# ADC_PLL.net
KiCad netlist of a schematic drawn in Altium Designer
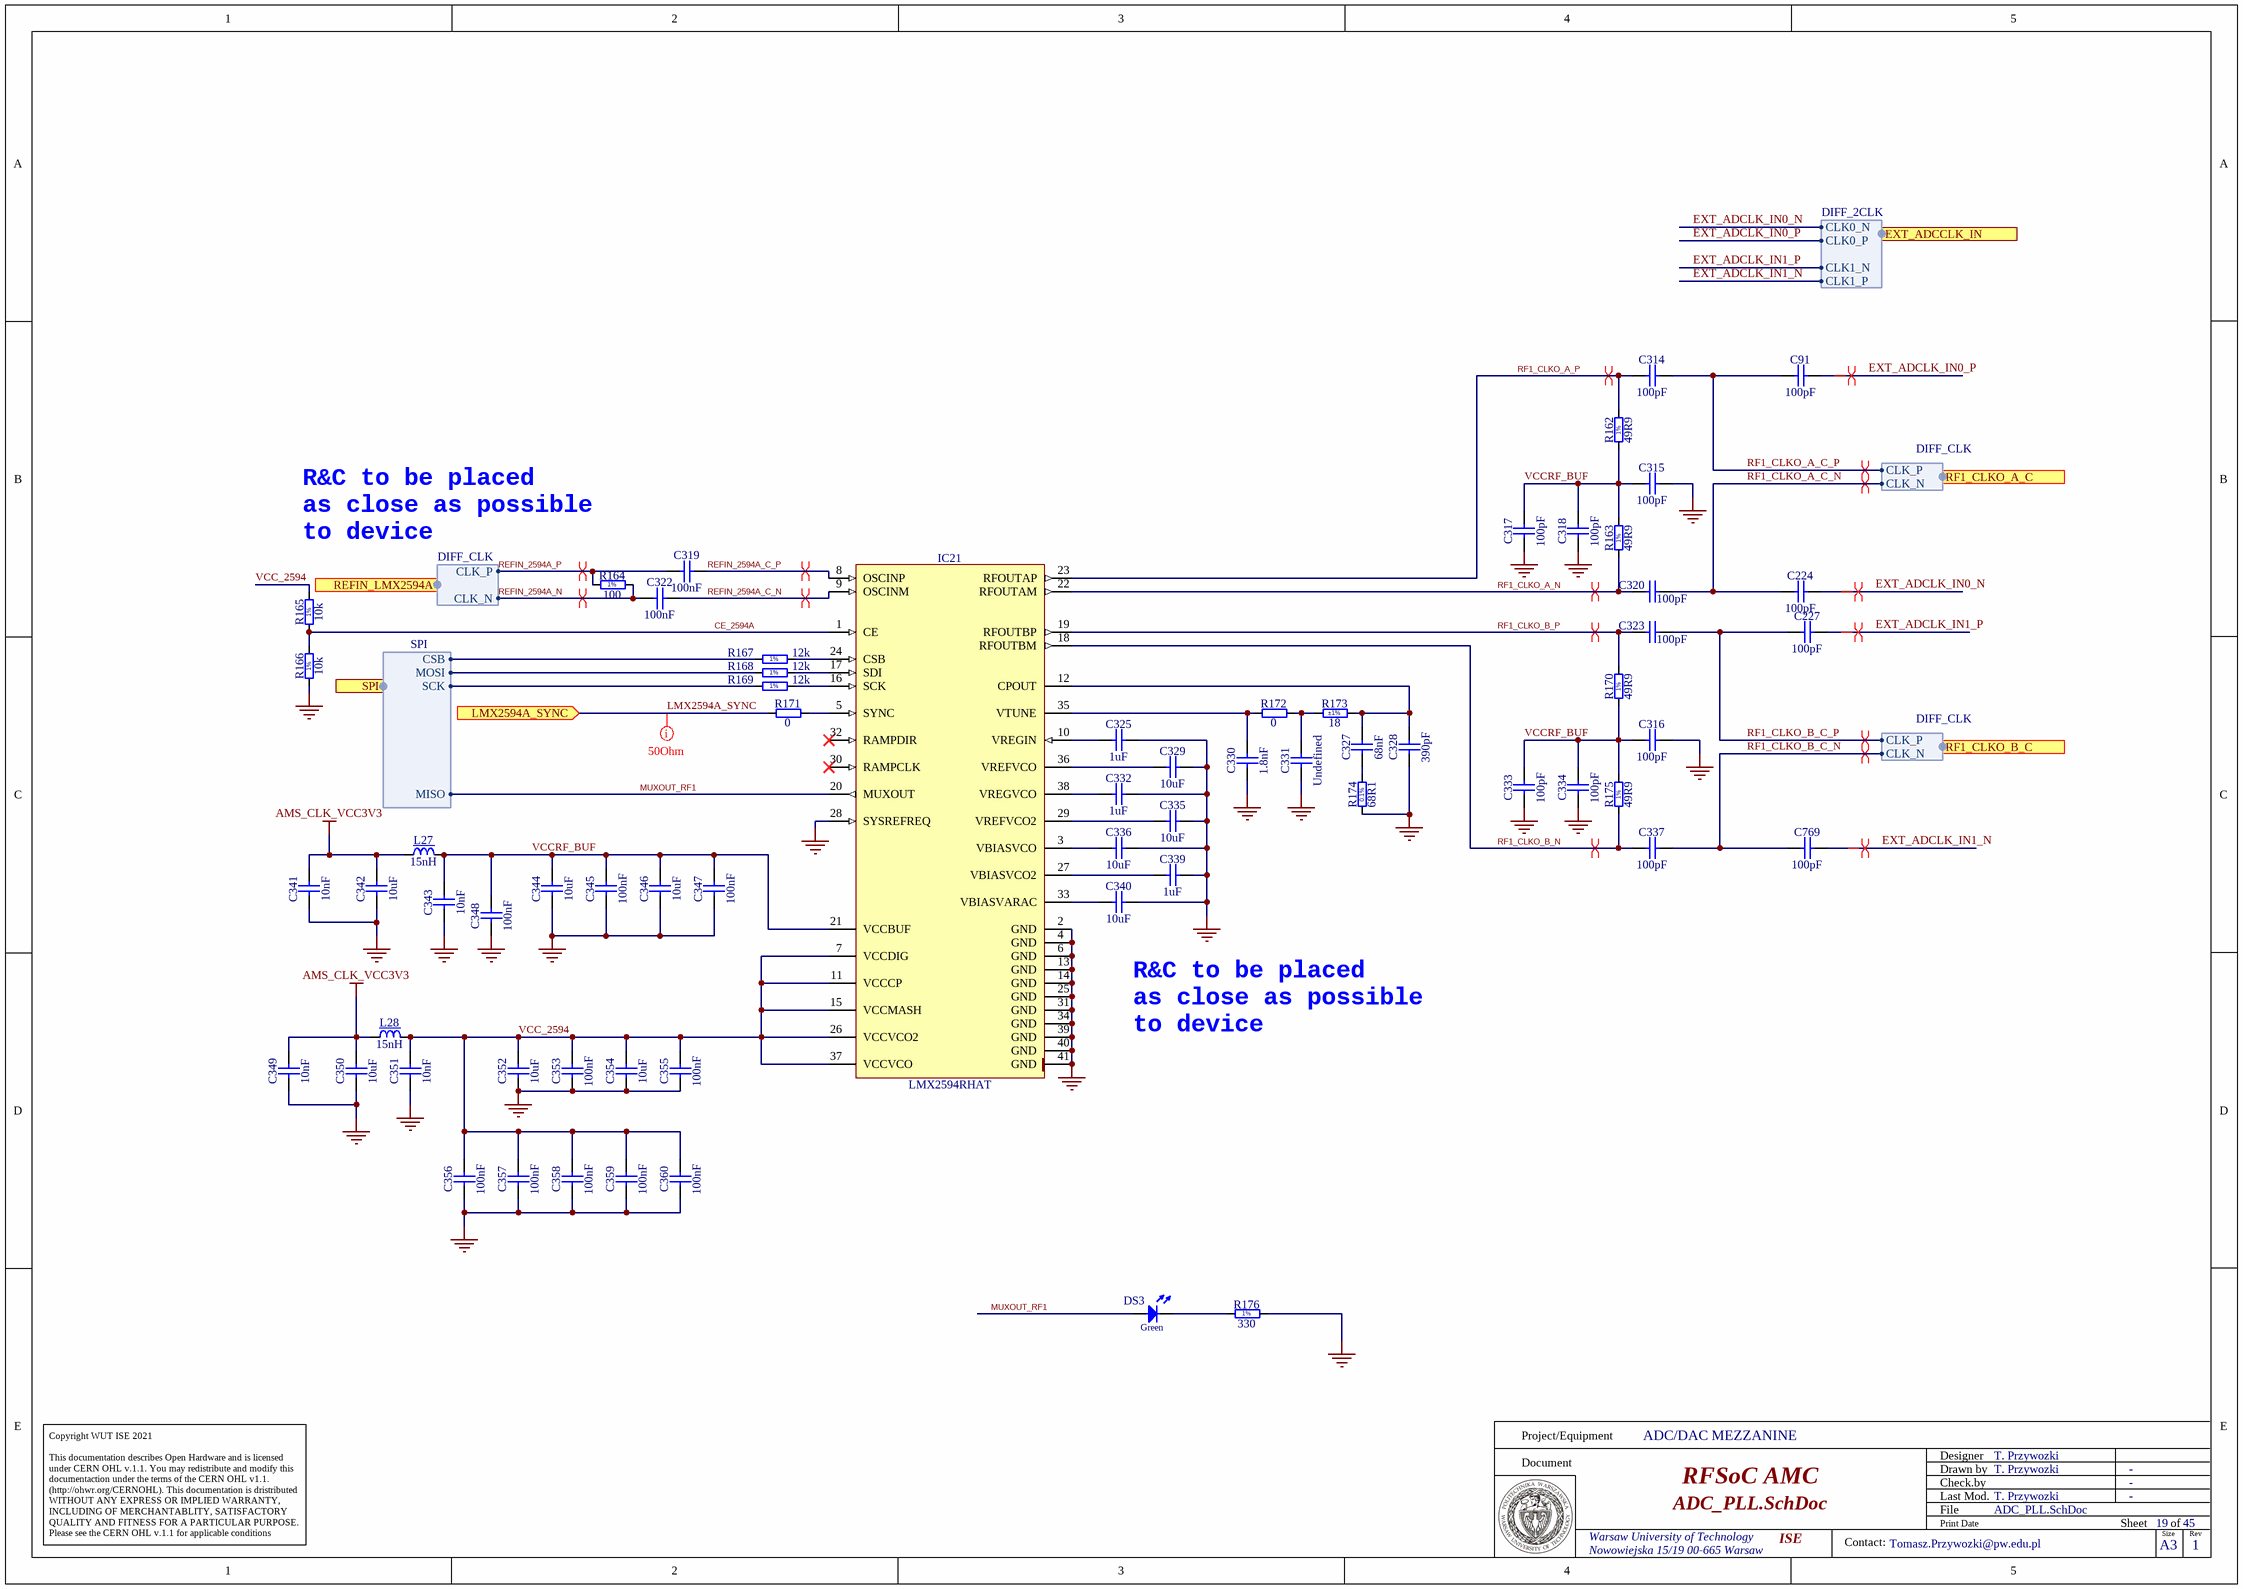
[diagram p0: ADC_PLL.SchDoc]

(export (version "E")
  (design (tool "Eeschema 10.0.6"))
  (components
    (comp (ref "C91")
      (value "100pF")
      (footprint "CAPC1005X55N")
      (description "Non-polarised capacitor")
      (fields
        (field (name "PART NUMBER") "CC0402_100PF_25V_5%_C0G_KEMET_HiQ-CBR")
        (field (name "VOLTAGE") "25V")
        (field (name "AUTHOR") "CERN DEM MR")
      )
      (libsource (lib "Capacitors") (part "Capacitor - non polarized"))
    )
    (comp (ref "C224")
      (value "100pF")
      (footprint "CAPC1005X55N")
      (description "Non-polarised capacitor")
      (fields
        (field (name "PART NUMBER") "CC0402_100PF_25V_5%_C0G_KEMET_HiQ-CBR")
        (field (name "VOLTAGE") "25V")
        (field (name "AUTHOR") "CERN DEM MR")
      )
      (libsource (lib "Capacitors") (part "Capacitor - non polarized"))
    )
    (comp (ref "C227")
      (value "100pF")
      (footprint "CAPC1005X55N")
      (description "Non-polarised capacitor")
      (fields
        (field (name "PART NUMBER") "CC0402_100PF_25V_5%_C0G_KEMET_HiQ-CBR")
        (field (name "VOLTAGE") "25V")
        (field (name "AUTHOR") "CERN DEM MR")
      )
      (libsource (lib "Capacitors") (part "Capacitor - non polarized"))
    )
    (comp (ref "C314")
      (value "100pF")
      (footprint "CAPC1005X55N")
      (description "Non-polarised capacitor")
      (fields
        (field (name "PART NUMBER") "CC0402_100PF_25V_5%_C0G_KEMET_HiQ-CBR")
        (field (name "VOLTAGE") "25V")
        (field (name "AUTHOR") "CERN DEM MR")
      )
      (libsource (lib "Capacitors") (part "Capacitor - non polarized"))
    )
    (comp (ref "C315")
      (value "100pF")
      (footprint "CAPC1005X55N")
      (description "Non-polarised capacitor")
      (fields
        (field (name "PART NUMBER") "CC0402_100PF_25V_5%_C0G_KEMET_HiQ-CBR")
        (field (name "VOLTAGE") "25V")
        (field (name "AUTHOR") "CERN DEM MR")
      )
      (libsource (lib "Capacitors") (part "Capacitor - non polarized"))
    )
    (comp (ref "C316")
      (value "100pF")
      (footprint "CAPC1005X55N")
      (description "Non-polarised capacitor")
      (fields
        (field (name "PART NUMBER") "CC0402_100PF_25V_5%_C0G_KEMET_HiQ-CBR")
        (field (name "VOLTAGE") "25V")
        (field (name "AUTHOR") "CERN DEM MR")
      )
      (libsource (lib "Capacitors") (part "Capacitor - non polarized"))
    )
    (comp (ref "C317")
      (value "100pF")
      (footprint "CAPC1005X55N")
      (description "Non-polarised capacitor")
      (fields
        (field (name "PART NUMBER") "CC0402_100PF_25V_5%_C0G_KEMET_HiQ-CBR")
        (field (name "VOLTAGE") "25V")
        (field (name "AUTHOR") "CERN DEM MR")
      )
      (libsource (lib "Capacitors") (part "Capacitor - non polarized"))
    )
    (comp (ref "C318")
      (value "100pF")
      (footprint "CAPC1005X55N")
      (description "Non-polarised capacitor")
      (fields
        (field (name "PART NUMBER") "CC0402_100PF_25V_5%_C0G_KEMET_HiQ-CBR")
        (field (name "VOLTAGE") "25V")
        (field (name "AUTHOR") "CERN DEM MR")
      )
      (libsource (lib "Capacitors") (part "Capacitor - non polarized"))
    )
    (comp (ref "C319")
      (value "100nF")
      (footprint "CAPC1005X55N")
      (description "Non-polarised capacitor")
      (fields
        (field (name "PART NUMBER") "CC0402_100NF_25V_10%_X7R_YUDEN_TMK105B7104KVHF")
        (field (name "VOLTAGE") "25V")
        (field (name "AUTHOR") "CERN DEM JLC")
      )
      (libsource (lib "Capacitors") (part "Capacitor - non polarized"))
    )
    (comp (ref "C320")
      (value "100pF")
      (footprint "CAPC1005X55N")
      (description "Non-polarised capacitor")
      (fields
        (field (name "PART NUMBER") "CC0402_100PF_25V_5%_C0G_KEMET_HiQ-CBR")
        (field (name "VOLTAGE") "25V")
        (field (name "AUTHOR") "CERN DEM MR")
      )
      (libsource (lib "Capacitors") (part "Capacitor - non polarized"))
    )
    (comp (ref "C322")
      (value "100nF")
      (footprint "CAPC1005X55N")
      (description "Non-polarised capacitor")
      (fields
        (field (name "PART NUMBER") "CC0402_100NF_25V_10%_X7R_YUDEN_TMK105B7104KVHF")
        (field (name "VOLTAGE") "25V")
        (field (name "AUTHOR") "CERN DEM JLC")
      )
      (libsource (lib "Capacitors") (part "Capacitor - non polarized"))
    )
    (comp (ref "C323")
      (value "100pF")
      (footprint "CAPC1005X55N")
      (description "Non-polarised capacitor")
      (fields
        (field (name "PART NUMBER") "CC0402_100PF_25V_5%_C0G_KEMET_HiQ-CBR")
        (field (name "VOLTAGE") "25V")
        (field (name "AUTHOR") "CERN DEM MR")
      )
      (libsource (lib "Capacitors") (part "Capacitor - non polarized"))
    )
    (comp (ref "C325")
      (value "1uF")
      (footprint "CAPC1005X55N")
      (description "Non-polarised capacitor")
      (fields
        (field (name "PART NUMBER") "CC0402_1UF_16V_10%_X5R")
        (field (name "VOLTAGE") "16V")
        (field (name "AUTHOR") "CERN DEM JLC")
      )
      (libsource (lib "Capacitors") (part "Capacitor - non polarized"))
    )
    (comp (ref "C327")
      (value "68nF")
      (footprint "CAPC1005X55N")
      (description "Non-polarised capacitor")
      (fields
        (field (name "PART NUMBER") "CC0402_68NF_16V_10%_X7R")
        (field (name "VOLTAGE") "16V")
        (field (name "AUTHOR") "CERN DEM JLC")
      )
      (libsource (lib "Capacitors") (part "Capacitor - non polarized"))
    )
    (comp (ref "C328")
      (value "390pF")
      (footprint "CAPC1608X87N")
      (description "Non-polarised capacitor")
      (fields
        (field (name "PART NUMBER") "CC0603_390PF_50V_5%_NP0")
        (field (name "VOLTAGE") "50V")
        (field (name "AUTHOR") "CERN DEM JLC")
      )
      (libsource (lib "Capacitors") (part "Capacitor - non polarized"))
    )
    (comp (ref "C329")
      (value "10uF")
      (footprint "CAPC1608X80N")
      (description "Non-polarised capacitor")
      (fields
        (field (name "PART NUMBER") "CC0603_10UF_10V_10%_X5R")
        (field (name "VOLTAGE") "10V")
        (field (name "AUTHOR") "CERN DEM JLC")
      )
      (libsource (lib "Capacitors") (part "Capacitor - non polarized"))
    )
    (comp (ref "C330")
      (value "1.8nF")
      (footprint "CAPC1608X87N")
      (description "Non-polarised capacitor")
      (fields
        (field (name "PART NUMBER") "CC0603_1.8NF_50V_5%_X7R")
        (field (name "VOLTAGE") "50V")
        (field (name "AUTHOR") "CERN DEM JLC")
      )
      (libsource (lib "Capacitors") (part "Capacitor - non polarized"))
    )
    (comp (ref "C331")
      (value "Undefined")
      (footprint "CAPC1005X55N")
      (description "Non-polarised capacitor")
      (fields (field (name "PART NUMBER") "CC0402_NO-VALUE") (field (name "AUTHOR") "CERN DEM JLC"))
      (libsource (lib "Capacitors") (part "Capacitor - non polarized"))
    )
    (comp (ref "C332")
      (value "1uF")
      (footprint "CAPC1005X55N")
      (description "Non-polarised capacitor")
      (fields
        (field (name "PART NUMBER") "CC0402_1UF_16V_10%_X5R")
        (field (name "VOLTAGE") "16V")
        (field (name "AUTHOR") "CERN DEM JLC")
      )
      (libsource (lib "Capacitors") (part "Capacitor - non polarized"))
    )
    (comp (ref "C333")
      (value "100pF")
      (footprint "CAPC1005X55N")
      (description "Non-polarised capacitor")
      (fields
        (field (name "PART NUMBER") "CC0402_100PF_25V_5%_C0G_KEMET_HiQ-CBR")
        (field (name "VOLTAGE") "25V")
        (field (name "AUTHOR") "CERN DEM MR")
      )
      (libsource (lib "Capacitors") (part "Capacitor - non polarized"))
    )
    (comp (ref "C334")
      (value "100pF")
      (footprint "CAPC1005X55N")
      (description "Non-polarised capacitor")
      (fields
        (field (name "PART NUMBER") "CC0402_100PF_25V_5%_C0G_KEMET_HiQ-CBR")
        (field (name "VOLTAGE") "25V")
        (field (name "AUTHOR") "CERN DEM MR")
      )
      (libsource (lib "Capacitors") (part "Capacitor - non polarized"))
    )
    (comp (ref "C335")
      (value "10uF")
      (footprint "CAPC1608X80N")
      (description "Non-polarised capacitor")
      (fields
        (field (name "PART NUMBER") "CC0603_10UF_10V_10%_X5R")
        (field (name "VOLTAGE") "10V")
        (field (name "AUTHOR") "CERN DEM JLC")
      )
      (libsource (lib "Capacitors") (part "Capacitor - non polarized"))
    )
    (comp (ref "C336")
      (value "10uF")
      (footprint "CAPC1608X80N")
      (description "Non-polarised capacitor")
      (fields
        (field (name "PART NUMBER") "CC0603_10UF_10V_10%_X5R")
        (field (name "VOLTAGE") "10V")
        (field (name "AUTHOR") "CERN DEM JLC")
      )
      (libsource (lib "Capacitors") (part "Capacitor - non polarized"))
    )
    (comp (ref "C337")
      (value "100pF")
      (footprint "CAPC1005X55N")
      (description "Non-polarised capacitor")
      (fields
        (field (name "PART NUMBER") "CC0402_100PF_25V_5%_C0G_KEMET_HiQ-CBR")
        (field (name "VOLTAGE") "25V")
        (field (name "AUTHOR") "CERN DEM MR")
      )
      (libsource (lib "Capacitors") (part "Capacitor - non polarized"))
    )
    (comp (ref "C339")
      (value "1uF")
      (footprint "CAPC1005X55N")
      (description "Non-polarised capacitor")
      (fields
        (field (name "PART NUMBER") "CC0402_1UF_16V_10%_X5R")
        (field (name "VOLTAGE") "16V")
        (field (name "AUTHOR") "CERN DEM JLC")
      )
      (libsource (lib "Capacitors") (part "Capacitor - non polarized"))
    )
    (comp (ref "C340")
      (value "10uF")
      (footprint "CAPC1608X80N")
      (description "Non-polarised capacitor")
      (fields
        (field (name "PART NUMBER") "CC0603_10UF_10V_10%_X5R")
        (field (name "VOLTAGE") "10V")
        (field (name "AUTHOR") "CERN DEM JLC")
      )
      (libsource (lib "Capacitors") (part "Capacitor - non polarized"))
    )
    (comp (ref "C341")
      (value "10nF")
      (footprint "CAPC1005X55N")
      (description "Non-polarised capacitor")
      (fields
        (field (name "PART NUMBER") "CC0402_10NF_16V_10%_X7R")
        (field (name "VOLTAGE") "16V")
        (field (name "AUTHOR") "CERN DEM JLC")
      )
      (libsource (lib "Capacitors") (part "Capacitor - non polarized"))
    )
    (comp (ref "C342")
      (value "10uF")
      (footprint "CAPC1608X80N")
      (description "Non-polarised capacitor")
      (fields
        (field (name "PART NUMBER") "CC0603_10UF_10V_10%_X5R")
        (field (name "VOLTAGE") "10V")
        (field (name "AUTHOR") "CERN DEM JLC")
      )
      (libsource (lib "Capacitors") (part "Capacitor - non polarized"))
    )
    (comp (ref "C343")
      (value "10nF")
      (footprint "CAPC1005X55N")
      (description "Non-polarised capacitor")
      (fields
        (field (name "PART NUMBER") "CC0402_10NF_16V_10%_X7R")
        (field (name "VOLTAGE") "16V")
        (field (name "AUTHOR") "CERN DEM JLC")
      )
      (libsource (lib "Capacitors") (part "Capacitor - non polarized"))
    )
    (comp (ref "C344")
      (value "10uF")
      (footprint "CAPC1608X80N")
      (description "Non-polarised capacitor")
      (fields
        (field (name "PART NUMBER") "CC0603_10UF_10V_10%_X5R")
        (field (name "VOLTAGE") "10V")
        (field (name "AUTHOR") "CERN DEM JLC")
      )
      (libsource (lib "Capacitors") (part "Capacitor - non polarized"))
    )
    (comp (ref "C345")
      (value "100nF")
      (footprint "CAPC1005X55N")
      (description "Non-polarised capacitor")
      (fields
        (field (name "PART NUMBER") "CC0402_100NF_25V_10%_X7R_YUDEN_TMK105B7104KVHF")
        (field (name "VOLTAGE") "25V")
        (field (name "AUTHOR") "CERN DEM JLC")
      )
      (libsource (lib "Capacitors") (part "Capacitor - non polarized"))
    )
    (comp (ref "C346")
      (value "10uF")
      (footprint "CAPC1608X80N")
      (description "Non-polarised capacitor")
      (fields
        (field (name "PART NUMBER") "CC0603_10UF_10V_10%_X5R")
        (field (name "VOLTAGE") "10V")
        (field (name "AUTHOR") "CERN DEM JLC")
      )
      (libsource (lib "Capacitors") (part "Capacitor - non polarized"))
    )
    (comp (ref "C347")
      (value "100nF")
      (footprint "CAPC1005X55N")
      (description "Non-polarised capacitor")
      (fields
        (field (name "PART NUMBER") "CC0402_100NF_25V_10%_X7R_YUDEN_TMK105B7104KVHF")
        (field (name "VOLTAGE") "25V")
        (field (name "AUTHOR") "CERN DEM JLC")
      )
      (libsource (lib "Capacitors") (part "Capacitor - non polarized"))
    )
    (comp (ref "C348")
      (value "100nF")
      (footprint "CAPC1005X55N")
      (description "Non-polarised capacitor")
      (fields
        (field (name "PART NUMBER") "CC0402_100NF_25V_10%_X7R_YUDEN_TMK105B7104KVHF")
        (field (name "VOLTAGE") "25V")
        (field (name "AUTHOR") "CERN DEM JLC")
      )
      (libsource (lib "Capacitors") (part "Capacitor - non polarized"))
    )
    (comp (ref "C349")
      (value "10nF")
      (footprint "CAPC1005X55N")
      (description "Non-polarised capacitor")
      (fields
        (field (name "PART NUMBER") "CC0402_10NF_16V_10%_X7R")
        (field (name "VOLTAGE") "16V")
        (field (name "AUTHOR") "CERN DEM JLC")
      )
      (libsource (lib "Capacitors") (part "Capacitor - non polarized"))
    )
    (comp (ref "C350")
      (value "10uF")
      (footprint "CAPC1608X80N")
      (description "Non-polarised capacitor")
      (fields
        (field (name "PART NUMBER") "CC0603_10UF_10V_10%_X5R")
        (field (name "VOLTAGE") "10V")
        (field (name "AUTHOR") "CERN DEM JLC")
      )
      (libsource (lib "Capacitors") (part "Capacitor - non polarized"))
    )
    (comp (ref "C351")
      (value "10nF")
      (footprint "CAPC1005X55N")
      (description "Non-polarised capacitor")
      (fields
        (field (name "PART NUMBER") "CC0402_10NF_16V_10%_X7R")
        (field (name "VOLTAGE") "16V")
        (field (name "AUTHOR") "CERN DEM JLC")
      )
      (libsource (lib "Capacitors") (part "Capacitor - non polarized"))
    )
    (comp (ref "C352")
      (value "10uF")
      (footprint "CAPC1608X80N")
      (description "Non-polarised capacitor")
      (fields
        (field (name "PART NUMBER") "CC0603_10UF_10V_10%_X5R")
        (field (name "VOLTAGE") "10V")
        (field (name "AUTHOR") "CERN DEM JLC")
      )
      (libsource (lib "Capacitors") (part "Capacitor - non polarized"))
    )
    (comp (ref "C353")
      (value "100nF")
      (footprint "CAPC1005X55N")
      (description "Non-polarised capacitor")
      (fields
        (field (name "PART NUMBER") "CC0402_100NF_25V_10%_X7R_YUDEN_TMK105B7104KVHF")
        (field (name "VOLTAGE") "25V")
        (field (name "AUTHOR") "CERN DEM JLC")
      )
      (libsource (lib "Capacitors") (part "Capacitor - non polarized"))
    )
    (comp (ref "C354")
      (value "10uF")
      (footprint "CAPC1608X80N")
      (description "Non-polarised capacitor")
      (fields
        (field (name "PART NUMBER") "CC0603_10UF_10V_10%_X5R")
        (field (name "VOLTAGE") "10V")
        (field (name "AUTHOR") "CERN DEM JLC")
      )
      (libsource (lib "Capacitors") (part "Capacitor - non polarized"))
    )
    (comp (ref "C355")
      (value "100nF")
      (footprint "CAPC1005X55N")
      (description "Non-polarised capacitor")
      (fields
        (field (name "PART NUMBER") "CC0402_100NF_25V_10%_X7R_YUDEN_TMK105B7104KVHF")
        (field (name "VOLTAGE") "25V")
        (field (name "AUTHOR") "CERN DEM JLC")
      )
      (libsource (lib "Capacitors") (part "Capacitor - non polarized"))
    )
    (comp (ref "C356")
      (value "100nF")
      (footprint "CAPC1005X55N")
      (description "Non-polarised capacitor")
      (fields
        (field (name "PART NUMBER") "CC0402_100NF_25V_10%_X7R_YUDEN_TMK105B7104KVHF")
        (field (name "VOLTAGE") "25V")
        (field (name "AUTHOR") "CERN DEM JLC")
      )
      (libsource (lib "Capacitors") (part "Capacitor - non polarized"))
    )
    (comp (ref "C357")
      (value "100nF")
      (footprint "CAPC1005X55N")
      (description "Non-polarised capacitor")
      (fields
        (field (name "PART NUMBER") "CC0402_100NF_25V_10%_X7R_YUDEN_TMK105B7104KVHF")
        (field (name "VOLTAGE") "25V")
        (field (name "AUTHOR") "CERN DEM JLC")
      )
      (libsource (lib "Capacitors") (part "Capacitor - non polarized"))
    )
    (comp (ref "C358")
      (value "100nF")
      (footprint "CAPC1005X55N")
      (description "Non-polarised capacitor")
      (fields
        (field (name "PART NUMBER") "CC0402_100NF_25V_10%_X7R_YUDEN_TMK105B7104KVHF")
        (field (name "VOLTAGE") "25V")
        (field (name "AUTHOR") "CERN DEM JLC")
      )
      (libsource (lib "Capacitors") (part "Capacitor - non polarized"))
    )
    (comp (ref "C359")
      (value "100nF")
      (footprint "CAPC1005X55N")
      (description "Non-polarised capacitor")
      (fields
        (field (name "PART NUMBER") "CC0402_100NF_25V_10%_X7R_YUDEN_TMK105B7104KVHF")
        (field (name "VOLTAGE") "25V")
        (field (name "AUTHOR") "CERN DEM JLC")
      )
      (libsource (lib "Capacitors") (part "Capacitor - non polarized"))
    )
    (comp (ref "C360")
      (value "100nF")
      (footprint "CAPC1005X55N")
      (description "Non-polarised capacitor")
      (fields
        (field (name "PART NUMBER") "CC0402_100NF_25V_10%_X7R_YUDEN_TMK105B7104KVHF")
        (field (name "VOLTAGE") "25V")
        (field (name "AUTHOR") "CERN DEM JLC")
      )
      (libsource (lib "Capacitors") (part "Capacitor - non polarized"))
    )
    (comp (ref "C769")
      (value "100pF")
      (footprint "CAPC1005X55N")
      (description "Non-polarised capacitor")
      (fields
        (field (name "PART NUMBER") "CC0402_100PF_25V_5%_C0G_KEMET_HiQ-CBR")
        (field (name "VOLTAGE") "25V")
        (field (name "AUTHOR") "CERN DEM MR")
      )
      (libsource (lib "Capacitors") (part "Capacitor - non polarized"))
    )
    (comp (ref "DS3")
      (value "Green")
      (footprint "LED_OSRAM_LGL29K")
      (description "LED Green 1C 2A")
      (fields
        (field (name "PART NUMBER") "LED_OSRAM_LG L29K-G2J1-24-Z")
        (field (name "MANUFACTURER") "OSRAM")
        (field (name "AUTHOR") "CERN DEM JLC")
      )
      (libsource (lib "ICs And Semiconductors") (part "LED Green 1C 2A"))
    )
    (comp (ref "IC21")
      (value "LMX2594RHAT")
      (footprint "QFN50P600X600X100-41N-S460")
      (description "15GHz Wideband PLLatinum RF Synthesizer with Phase Synchronization and JESD204B Support")
      (fields (field (name "MANUFACTURER") "TEXAS INSTRUMENTS") (field (name "AUTHOR") "CERN DEM JLC"))
      (libsource (lib "ICs And Semiconductors") (part "LMX2594"))
    )
    (comp (ref "L27")
      (value "15nH")
      (footprint "IND_COILCRAFT_0402DC")
      (description "Inductor With Core")
      (fields
        (field (name "PART NUMBER") "IND0402_15NH_2%_COILCRAFT_0402DC")
        (field (name "POWER") "1A")
        (field (name "AUTHOR") "CERN DEM JLC")
      )
      (libsource (lib "Inductors & Transformers") (part "Inductor With Magnetic core"))
    )
    (comp (ref "L28")
      (value "15nH")
      (footprint "IND_COILCRAFT_0402DC")
      (description "Inductor With Core")
      (fields
        (field (name "PART NUMBER") "IND0402_15NH_2%_COILCRAFT_0402DC")
        (field (name "POWER") "1A")
        (field (name "AUTHOR") "CERN DEM JLC")
      )
      (libsource (lib "Inductors & Transformers") (part "Inductor With Magnetic core"))
    )
    (comp (ref "R162")
      (value "49R9")
      (footprint "RESC1005X40N")
      (description "Resistor - 1%")
      (fields
        (field (name "PART NUMBER") "R0402_49R9_1%_0.0625W_100PPM")
        (field (name "POWER") "0.0625W")
        (field (name "AUTHOR") "CERN DEM JLC")
      )
      (libsource (lib "Resistors") (part "Resistor - 1%"))
    )
    (comp (ref "R163")
      (value "49R9")
      (footprint "RESC1005X40N")
      (description "Resistor - 1%")
      (fields
        (field (name "PART NUMBER") "R0402_49R9_1%_0.0625W_100PPM")
        (field (name "POWER") "0.0625W")
        (field (name "AUTHOR") "CERN DEM JLC")
      )
      (libsource (lib "Resistors") (part "Resistor - 1%"))
    )
    (comp (ref "R164")
      (value "100")
      (footprint "RESC1005X40N")
      (description "Resistor - 1%")
      (fields
        (field (name "PART NUMBER") "R0402_100R_1%_0.1W_100PPM")
        (field (name "POWER") "0.1W")
        (field (name "AUTHOR") "CERN DEM JLC")
      )
      (libsource (lib "Resistors") (part "Resistor - 1%"))
    )
    (comp (ref "R165")
      (value "10k")
      (footprint "RESC1005X40N")
      (description "Resistor - 1%")
      (fields
        (field (name "PART NUMBER") "R0402_10K_1%_0.0625W_100PPM")
        (field (name "POWER") "0.0625W")
        (field (name "AUTHOR") "CERN DEM JLC")
      )
      (libsource (lib "Resistors") (part "Resistor - 1%"))
    )
    (comp (ref "R166")
      (value "10k")
      (footprint "RESC1005X40N")
      (description "Resistor - 1%")
      (fields
        (field (name "PART NUMBER") "R0402_10K_1%_0.0625W_100PPM")
        (field (name "POWER") "0.0625W")
        (field (name "AUTHOR") "CERN DEM JLC")
      )
      (libsource (lib "Resistors") (part "Resistor - 1%"))
    )
    (comp (ref "R167")
      (value "12k")
      (footprint "RESC1005X40N")
      (description "Resistor - 1%")
      (fields
        (field (name "PART NUMBER") "R0402_12K_1%_0.0625W_100PPM")
        (field (name "POWER") "0.0625W")
        (field (name "AUTHOR") "CERN DEM JLC")
      )
      (libsource (lib "Resistors") (part "Resistor - 1%"))
    )
    (comp (ref "R168")
      (value "12k")
      (footprint "RESC1005X40N")
      (description "Resistor - 1%")
      (fields
        (field (name "PART NUMBER") "R0402_12K_1%_0.0625W_100PPM")
        (field (name "POWER") "0.0625W")
        (field (name "AUTHOR") "CERN DEM JLC")
      )
      (libsource (lib "Resistors") (part "Resistor - 1%"))
    )
    (comp (ref "R169")
      (value "12k")
      (footprint "RESC1005X40N")
      (description "Resistor - 1%")
      (fields
        (field (name "PART NUMBER") "R0402_12K_1%_0.0625W_100PPM")
        (field (name "POWER") "0.0625W")
        (field (name "AUTHOR") "CERN DEM JLC")
      )
      (libsource (lib "Resistors") (part "Resistor - 1%"))
    )
    (comp (ref "R170")
      (value "49R9")
      (footprint "RESC1005X40N")
      (description "Resistor - 1%")
      (fields
        (field (name "PART NUMBER") "R0402_49R9_1%_0.0625W_100PPM")
        (field (name "POWER") "0.0625W")
        (field (name "AUTHOR") "CERN DEM JLC")
      )
      (libsource (lib "Resistors") (part "Resistor - 1%"))
    )
    (comp (ref "R171")
      (value "0")
      (footprint "RESC1005X40N")
      (description "Resistor")
      (fields
        (field (name "PART NUMBER") "R0402_0R_JUMPER")
        (field (name "MANUFACTURER") "GENERIC")
        (field (name "AUTHOR") "CERN DEM JLC")
      )
      (libsource (lib "Resistors") (part "Resistor"))
    )
    (comp (ref "R172")
      (value "0")
      (footprint "RESC1005X40N")
      (description "Resistor")
      (fields
        (field (name "PART NUMBER") "R0402_0R_JUMPER")
        (field (name "MANUFACTURER") "GENERIC")
        (field (name "AUTHOR") "CERN DEM JLC")
      )
      (libsource (lib "Resistors") (part "Resistor"))
    )
    (comp (ref "R173")
      (value "18")
      (footprint "RESC1005X40N")
      (description "Resistor - 1%")
      (fields
        (field (name "TOLERANCE") "±1%")
        (field (name "PART NUMBER") "R0402_18R_1%_0.0625W_100PPM")
        (field (name "POWER") "0.0625W")
        (field (name "AUTHOR") "CERN DEM JLC")
      )
      (libsource (lib "Resistors") (part "Resistor - 1%"))
    )
    (comp (ref "R174")
      (value "68R1")
      (footprint "RESC1608X55N")
      (description "Resistor - 0.1%")
      (fields
        (field (name "PART NUMBER") "R0603_68R1_0.1%_0.063W_10PPM")
        (field (name "POWER") "0.063W")
        (field (name "AUTHOR") "CERN DEM JLC")
      )
      (libsource (lib "Resistors") (part "Resistor - 0.1%"))
    )
    (comp (ref "R175")
      (value "49R9")
      (footprint "RESC1005X40N")
      (description "Resistor - 1%")
      (fields
        (field (name "PART NUMBER") "R0402_49R9_1%_0.0625W_100PPM")
        (field (name "POWER") "0.0625W")
        (field (name "AUTHOR") "CERN DEM JLC")
      )
      (libsource (lib "Resistors") (part "Resistor - 1%"))
    )
    (comp (ref "R176")
      (value "330")
      (footprint "RESC1005X40N")
      (description "Resistor - 1%")
      (fields
        (field (name "PART NUMBER") "R0402_330R_1%_0.0625W_100PPM")
        (field (name "POWER") "0.0625W")
        (field (name "AUTHOR") "CERN DEM JLC")
      )
      (libsource (lib "Resistors") (part "Resistor - 1%"))
    )
  )
  (nets
    (net (code "4") (name "/CE_2594A") (class "Default")
      (node (ref "IC21") (pin "1") (pinfunction "CE_1") (pintype "input"))
      (node (ref "R165") (pin "1") (pinfunction "1_1") (pintype "passive"))
      (node (ref "R166") (pin "2") (pinfunction "2_2") (pintype "passive"))
    )
    (net (code "5") (name "/CSB") (class "Default")
      (node (ref "R167") (pin "2") (pinfunction "2_2") (pintype "passive"))
    )
    (net (code "6") (name "/EXT_ADCLK_IN0_N") (class "Default")
      (node (ref "C224") (pin "2") (pinfunction "2_2") (pintype "passive"))
    )
    (net (code "7") (name "/EXT_ADCLK_IN0_P") (class "Default")
      (node (ref "C91") (pin "2") (pinfunction "2_2") (pintype "passive"))
    )
    (net (code "8") (name "/EXT_ADCLK_IN1_N") (class "Default")
      (node (ref "C769") (pin "2") (pinfunction "2_2") (pintype "passive"))
    )
    (net (code "9") (name "/EXT_ADCLK_IN1_P") (class "Default")
      (node (ref "C227") (pin "2") (pinfunction "2_2") (pintype "passive"))
    )
    (net (code "10") (name "/LMX2594A_SYNC") (class "Default")
      (node (ref "R171") (pin "1") (pinfunction "1_1") (pintype "passive"))
    )
    (net (code "11") (name "/MOSI") (class "Default")
      (node (ref "R168") (pin "2") (pinfunction "2_2") (pintype "passive"))
    )
    (net (code "12") (name "/MUXOUT_RF1") (class "Default")
      (node (ref "DS3") (pin "2") (pinfunction "A_2") (pintype "passive"))
      (node (ref "IC21") (pin "20") (pinfunction "MUXOUT_20") (pintype "output"))
    )
    (net (code "13") (name "/REFIN_2594A_C_N") (class "Default")
      (node (ref "C322") (pin "2") (pinfunction "2_2") (pintype "passive"))
      (node (ref "IC21") (pin "9") (pinfunction "OSCINM_9") (pintype "input"))
    )
    (net (code "14") (name "/REFIN_2594A_C_P") (class "Default")
      (node (ref "C319") (pin "2") (pinfunction "2_2") (pintype "passive"))
      (node (ref "IC21") (pin "8") (pinfunction "OSCINP_8") (pintype "input"))
    )
    (net (code "15") (name "/REFIN_2594A_N") (class "Default")
      (node (ref "C322") (pin "1") (pinfunction "1_1") (pintype "passive"))
      (node (ref "R164") (pin "2") (pinfunction "2_2") (pintype "passive"))
    )
    (net (code "16") (name "/REFIN_2594A_P") (class "Default")
      (node (ref "C319") (pin "1") (pinfunction "1_1") (pintype "passive"))
      (node (ref "R164") (pin "1") (pinfunction "1_1") (pintype "passive"))
    )
    (net (code "17") (name "/RF1_CLKO_A_C_N") (class "Default")
      (node (ref "C224") (pin "1") (pinfunction "1_1") (pintype "passive"))
      (node (ref "C320") (pin "2") (pinfunction "2_2") (pintype "passive"))
    )
    (net (code "18") (name "/RF1_CLKO_A_C_P") (class "Default")
      (node (ref "C314") (pin "2") (pinfunction "2_2") (pintype "passive"))
      (node (ref "C91") (pin "1") (pinfunction "1_1") (pintype "passive"))
    )
    (net (code "19") (name "/RF1_CLKO_A_N") (class "Default")
      (node (ref "C320") (pin "1") (pinfunction "1_1") (pintype "passive"))
      (node (ref "IC21") (pin "22") (pinfunction "RFOUTAM_22") (pintype "output"))
      (node (ref "R163") (pin "1") (pinfunction "1_1") (pintype "passive"))
    )
    (net (code "20") (name "/RF1_CLKO_A_P") (class "Default")
      (node (ref "C314") (pin "1") (pinfunction "1_1") (pintype "passive"))
      (node (ref "IC21") (pin "23") (pinfunction "RFOUTAP_23") (pintype "output"))
      (node (ref "R162") (pin "2") (pinfunction "2_2") (pintype "passive"))
    )
    (net (code "21") (name "/RF1_CLKO_B_C_N") (class "Default")
      (node (ref "C337") (pin "2") (pinfunction "2_2") (pintype "passive"))
      (node (ref "C769") (pin "1") (pinfunction "1_1") (pintype "passive"))
    )
    (net (code "22") (name "/RF1_CLKO_B_C_P") (class "Default")
      (node (ref "C227") (pin "1") (pinfunction "1_1") (pintype "passive"))
      (node (ref "C323") (pin "2") (pinfunction "2_2") (pintype "passive"))
    )
    (net (code "23") (name "/RF1_CLKO_B_N") (class "Default")
      (node (ref "C337") (pin "1") (pinfunction "1_1") (pintype "passive"))
      (node (ref "IC21") (pin "18") (pinfunction "RFOUTBM_18") (pintype "output"))
      (node (ref "R175") (pin "1") (pinfunction "1_1") (pintype "passive"))
    )
    (net (code "24") (name "/RF1_CLKO_B_P") (class "Default")
      (node (ref "C323") (pin "1") (pinfunction "1_1") (pintype "passive"))
      (node (ref "IC21") (pin "19") (pinfunction "RFOUTBP_19") (pintype "output"))
      (node (ref "R170") (pin "2") (pinfunction "2_2") (pintype "passive"))
    )
    (net (code "25") (name "/SCK") (class "Default")
      (node (ref "R169") (pin "2") (pinfunction "2_2") (pintype "passive"))
    )
    (net (code "26") (name "/VCCRF_BUF") (class "Default")
      (node (ref "C315") (pin "1") (pinfunction "1_1") (pintype "passive"))
      (node (ref "C316") (pin "1") (pinfunction "1_1") (pintype "passive"))
      (node (ref "C317") (pin "2") (pinfunction "2_2") (pintype "passive"))
      (node (ref "C318") (pin "2") (pinfunction "2_2") (pintype "passive"))
      (node (ref "C333") (pin "2") (pinfunction "2_2") (pintype "passive"))
      (node (ref "C334") (pin "2") (pinfunction "2_2") (pintype "passive"))
      (node (ref "C343") (pin "2") (pinfunction "2_2") (pintype "passive"))
      (node (ref "C344") (pin "2") (pinfunction "2_2") (pintype "passive"))
      (node (ref "C345") (pin "2") (pinfunction "2_2") (pintype "passive"))
      (node (ref "C346") (pin "2") (pinfunction "2_2") (pintype "passive"))
      (node (ref "C347") (pin "2") (pinfunction "2_2") (pintype "passive"))
      (node (ref "C348") (pin "2") (pinfunction "2_2") (pintype "passive"))
      (node (ref "IC21") (pin "21") (pinfunction "VCCBUF_21") (pintype "power_in"))
      (node (ref "L27") (pin "2") (pinfunction "2_2") (pintype "passive"))
      (node (ref "R162") (pin "1") (pinfunction "1_1") (pintype "passive"))
      (node (ref "R163") (pin "2") (pinfunction "2_2") (pintype "passive"))
      (node (ref "R170") (pin "1") (pinfunction "1_1") (pintype "passive"))
      (node (ref "R175") (pin "2") (pinfunction "2_2") (pintype "passive"))
    )
    (net (code "27") (name "/VCC_2594") (class "Default")
      (node (ref "C351") (pin "2") (pinfunction "2_2") (pintype "passive"))
      (node (ref "C352") (pin "2") (pinfunction "2_2") (pintype "passive"))
      (node (ref "C353") (pin "2") (pinfunction "2_2") (pintype "passive"))
      (node (ref "C354") (pin "2") (pinfunction "2_2") (pintype "passive"))
      (node (ref "C355") (pin "2") (pinfunction "2_2") (pintype "passive"))
      (node (ref "C356") (pin "2") (pinfunction "2_2") (pintype "passive"))
      (node (ref "C357") (pin "2") (pinfunction "2_2") (pintype "passive"))
      (node (ref "C358") (pin "2") (pinfunction "2_2") (pintype "passive"))
      (node (ref "C359") (pin "2") (pinfunction "2_2") (pintype "passive"))
      (node (ref "C360") (pin "2") (pinfunction "2_2") (pintype "passive"))
      (node (ref "IC21") (pin "11") (pinfunction "VCCCP_11") (pintype "power_in"))
      (node (ref "IC21") (pin "15") (pinfunction "VCCMASH_15") (pintype "power_in"))
      (node (ref "IC21") (pin "26") (pinfunction "VCCVCO2_26") (pintype "power_in"))
      (node (ref "IC21") (pin "37") (pinfunction "VCCVCO_37") (pintype "power_in"))
      (node (ref "IC21") (pin "7") (pinfunction "VCCDIG_7") (pintype "power_in"))
      (node (ref "L28") (pin "2") (pinfunction "2_2") (pintype "passive"))
      (node (ref "R165") (pin "2") (pinfunction "2_2") (pintype "passive"))
    )
    (net (code "31") (name "AMS_CLK_VCC3V3") (class "Default")
      (node (ref "C341") (pin "2") (pinfunction "2_2") (pintype "passive"))
      (node (ref "C342") (pin "2") (pinfunction "2_2") (pintype "passive"))
      (node (ref "C349") (pin "2") (pinfunction "2_2") (pintype "passive"))
      (node (ref "C350") (pin "2") (pinfunction "2_2") (pintype "passive"))
      (node (ref "L27") (pin "1") (pinfunction "1_1") (pintype "passive"))
      (node (ref "L28") (pin "1") (pinfunction "1_1") (pintype "passive"))
    )
    (net (code "32") (name "GND") (class "Default")
      (node (ref "C315") (pin "2") (pinfunction "2_2") (pintype "passive"))
      (node (ref "C316") (pin "2") (pinfunction "2_2") (pintype "passive"))
      (node (ref "C317") (pin "1") (pinfunction "1_1") (pintype "passive"))
      (node (ref "C318") (pin "1") (pinfunction "1_1") (pintype "passive"))
      (node (ref "C325") (pin "1") (pinfunction "1_1") (pintype "passive"))
      (node (ref "C328") (pin "1") (pinfunction "1_1") (pintype "passive"))
      (node (ref "C329") (pin "1") (pinfunction "1_1") (pintype "passive"))
      (node (ref "C330") (pin "1") (pinfunction "1_1") (pintype "passive"))
      (node (ref "C331") (pin "1") (pinfunction "1_1") (pintype "passive"))
      (node (ref "C332") (pin "1") (pinfunction "1_1") (pintype "passive"))
      (node (ref "C333") (pin "1") (pinfunction "1_1") (pintype "passive"))
      (node (ref "C334") (pin "1") (pinfunction "1_1") (pintype "passive"))
      (node (ref "C335") (pin "1") (pinfunction "1_1") (pintype "passive"))
      (node (ref "C336") (pin "1") (pinfunction "1_1") (pintype "passive"))
      (node (ref "C339") (pin "1") (pinfunction "1_1") (pintype "passive"))
      (node (ref "C340") (pin "1") (pinfunction "1_1") (pintype "passive"))
      (node (ref "C341") (pin "1") (pinfunction "1_1") (pintype "passive"))
      (node (ref "C342") (pin "1") (pinfunction "1_1") (pintype "passive"))
      (node (ref "C343") (pin "1") (pinfunction "1_1") (pintype "passive"))
      (node (ref "C344") (pin "1") (pinfunction "1_1") (pintype "passive"))
      (node (ref "C345") (pin "1") (pinfunction "1_1") (pintype "passive"))
      (node (ref "C346") (pin "1") (pinfunction "1_1") (pintype "passive"))
      (node (ref "C347") (pin "1") (pinfunction "1_1") (pintype "passive"))
      (node (ref "C348") (pin "1") (pinfunction "1_1") (pintype "passive"))
      (node (ref "C349") (pin "1") (pinfunction "1_1") (pintype "passive"))
      (node (ref "C350") (pin "1") (pinfunction "1_1") (pintype "passive"))
      (node (ref "C351") (pin "1") (pinfunction "1_1") (pintype "passive"))
      (node (ref "C352") (pin "1") (pinfunction "1_1") (pintype "passive"))
      (node (ref "C353") (pin "1") (pinfunction "1_1") (pintype "passive"))
      (node (ref "C354") (pin "1") (pinfunction "1_1") (pintype "passive"))
      (node (ref "C355") (pin "1") (pinfunction "1_1") (pintype "passive"))
      (node (ref "C356") (pin "1") (pinfunction "1_1") (pintype "passive"))
      (node (ref "C357") (pin "1") (pinfunction "1_1") (pintype "passive"))
      (node (ref "C358") (pin "1") (pinfunction "1_1") (pintype "passive"))
      (node (ref "C359") (pin "1") (pinfunction "1_1") (pintype "passive"))
      (node (ref "C360") (pin "1") (pinfunction "1_1") (pintype "passive"))
      (node (ref "IC21") (pin "13") (pinfunction "GND_13") (pintype "power_in"))
      (node (ref "IC21") (pin "14") (pinfunction "GND_14") (pintype "power_in"))
      (node (ref "IC21") (pin "2") (pinfunction "GND_2") (pintype "power_in"))
      (node (ref "IC21") (pin "25") (pinfunction "GND_25") (pintype "power_in"))
      (node (ref "IC21") (pin "28") (pinfunction "SYSREFREQ_28") (pintype "input"))
      (node (ref "IC21") (pin "31") (pinfunction "GND_31") (pintype "power_in"))
      (node (ref "IC21") (pin "34") (pinfunction "GND_34") (pintype "power_in"))
      (node (ref "IC21") (pin "39") (pinfunction "GND_39") (pintype "power_in"))
      (node (ref "IC21") (pin "4") (pinfunction "GND_4") (pintype "power_in"))
      (node (ref "IC21") (pin "40") (pinfunction "GND_40") (pintype "power_in"))
      (node (ref "IC21") (pin "41") (pinfunction "GND_41") (pintype "power_in"))
      (node (ref "IC21") (pin "6") (pinfunction "GND_6") (pintype "power_in"))
      (node (ref "R166") (pin "1") (pinfunction "1_1") (pintype "passive"))
      (node (ref "R174") (pin "1") (pinfunction "1_1") (pintype "passive"))
      (node (ref "R176") (pin "2") (pinfunction "2_2") (pintype "passive"))
    )
    (net (code "33") (name "Net-(C327-Pad1)") (class "Default")
      (node (ref "C327") (pin "1") (pinfunction "1_1") (pintype "passive"))
      (node (ref "R174") (pin "2") (pinfunction "2_2") (pintype "passive"))
    )
    (net (code "34") (name "Net-(C331-Pad2)") (class "Default")
      (node (ref "C331") (pin "2") (pinfunction "2_2") (pintype "passive"))
      (node (ref "R172") (pin "2") (pinfunction "2_2") (pintype "passive"))
      (node (ref "R173") (pin "1") (pinfunction "1_1") (pintype "passive"))
    )
    (net (code "35") (name "Net-(DS3-C)") (class "Default")
      (node (ref "DS3") (pin "1") (pinfunction "C_1") (pintype "passive"))
      (node (ref "R176") (pin "1") (pinfunction "1_1") (pintype "passive"))
    )
    (net (code "36") (name "Net-(IC21-CPOUT)") (class "Default")
      (node (ref "C327") (pin "2") (pinfunction "2_2") (pintype "passive"))
      (node (ref "C328") (pin "2") (pinfunction "2_2") (pintype "passive"))
      (node (ref "IC21") (pin "12") (pinfunction "CPOUT_12") (pintype "passive"))
      (node (ref "R173") (pin "2") (pinfunction "2_2") (pintype "passive"))
    )
    (net (code "37") (name "Net-(IC21-CSB)") (class "Default")
      (node (ref "IC21") (pin "24") (pinfunction "CSB_24") (pintype "input"))
      (node (ref "R167") (pin "1") (pinfunction "1_1") (pintype "passive"))
    )
    (net (code "38") (name "Net-(IC21-SCK)") (class "Default")
      (node (ref "IC21") (pin "16") (pinfunction "SCK_16") (pintype "input"))
      (node (ref "R169") (pin "1") (pinfunction "1_1") (pintype "passive"))
    )
    (net (code "39") (name "Net-(IC21-SDI)") (class "Default")
      (node (ref "IC21") (pin "17") (pinfunction "SDI_17") (pintype "input"))
      (node (ref "R168") (pin "1") (pinfunction "1_1") (pintype "passive"))
    )
    (net (code "40") (name "Net-(IC21-SYNC)") (class "Default")
      (node (ref "IC21") (pin "5") (pinfunction "SYNC_5") (pintype "input"))
      (node (ref "R171") (pin "2") (pinfunction "2_2") (pintype "passive"))
    )
    (net (code "41") (name "Net-(IC21-VBIASVARAC)") (class "Default")
      (node (ref "C340") (pin "2") (pinfunction "2_2") (pintype "passive"))
      (node (ref "IC21") (pin "33") (pinfunction "VBIASVARAC_33") (pintype "passive"))
    )
    (net (code "42") (name "Net-(IC21-VBIASVCO)") (class "Default")
      (node (ref "C336") (pin "2") (pinfunction "2_2") (pintype "passive"))
      (node (ref "IC21") (pin "3") (pinfunction "VBIASVCO_3") (pintype "passive"))
    )
    (net (code "43") (name "Net-(IC21-VBIASVCO2)") (class "Default")
      (node (ref "C339") (pin "2") (pinfunction "2_2") (pintype "passive"))
      (node (ref "IC21") (pin "27") (pinfunction "VBIASVCO2_27") (pintype "passive"))
    )
    (net (code "44") (name "Net-(IC21-VREFVCO)") (class "Default")
      (node (ref "C329") (pin "2") (pinfunction "2_2") (pintype "passive"))
      (node (ref "IC21") (pin "36") (pinfunction "VREFVCO_36") (pintype "passive"))
    )
    (net (code "45") (name "Net-(IC21-VREFVCO2)") (class "Default")
      (node (ref "C335") (pin "2") (pinfunction "2_2") (pintype "passive"))
      (node (ref "IC21") (pin "29") (pinfunction "VREFVCO2_29") (pintype "passive"))
    )
    (net (code "46") (name "Net-(IC21-VREGIN)") (class "Default")
      (node (ref "C325") (pin "2") (pinfunction "2_2") (pintype "passive"))
      (node (ref "IC21") (pin "10") (pinfunction "VREGIN_10") (pintype "input"))
    )
    (net (code "47") (name "Net-(IC21-VREGVCO)") (class "Default")
      (node (ref "C332") (pin "2") (pinfunction "2_2") (pintype "passive"))
      (node (ref "IC21") (pin "38") (pinfunction "VREGVCO_38") (pintype "passive"))
    )
    (net (code "48") (name "Net-(IC21-VTUNE)") (class "Default")
      (node (ref "C330") (pin "2") (pinfunction "2_2") (pintype "passive"))
      (node (ref "IC21") (pin "35") (pinfunction "VTUNE_35") (pintype "passive"))
      (node (ref "R172") (pin "1") (pinfunction "1_1") (pintype "passive"))
    )
    (net (code "49") (name "unconnected-(IC21-RAMPCLK-Pad30)") (class "Default")
      (node (ref "IC21") (pin "30") (pinfunction "RAMPCLK_30") (pintype "input+no_connect"))
    )
    (net (code "50") (name "unconnected-(IC21-RAMPDIR-Pad32)") (class "Default")
      (node (ref "IC21") (pin "32") (pinfunction "RAMPDIR_32") (pintype "input+no_connect"))
    )
  )
)
